# design.net
KiCad netlist of a schematic drawn in EasyEDA Pro
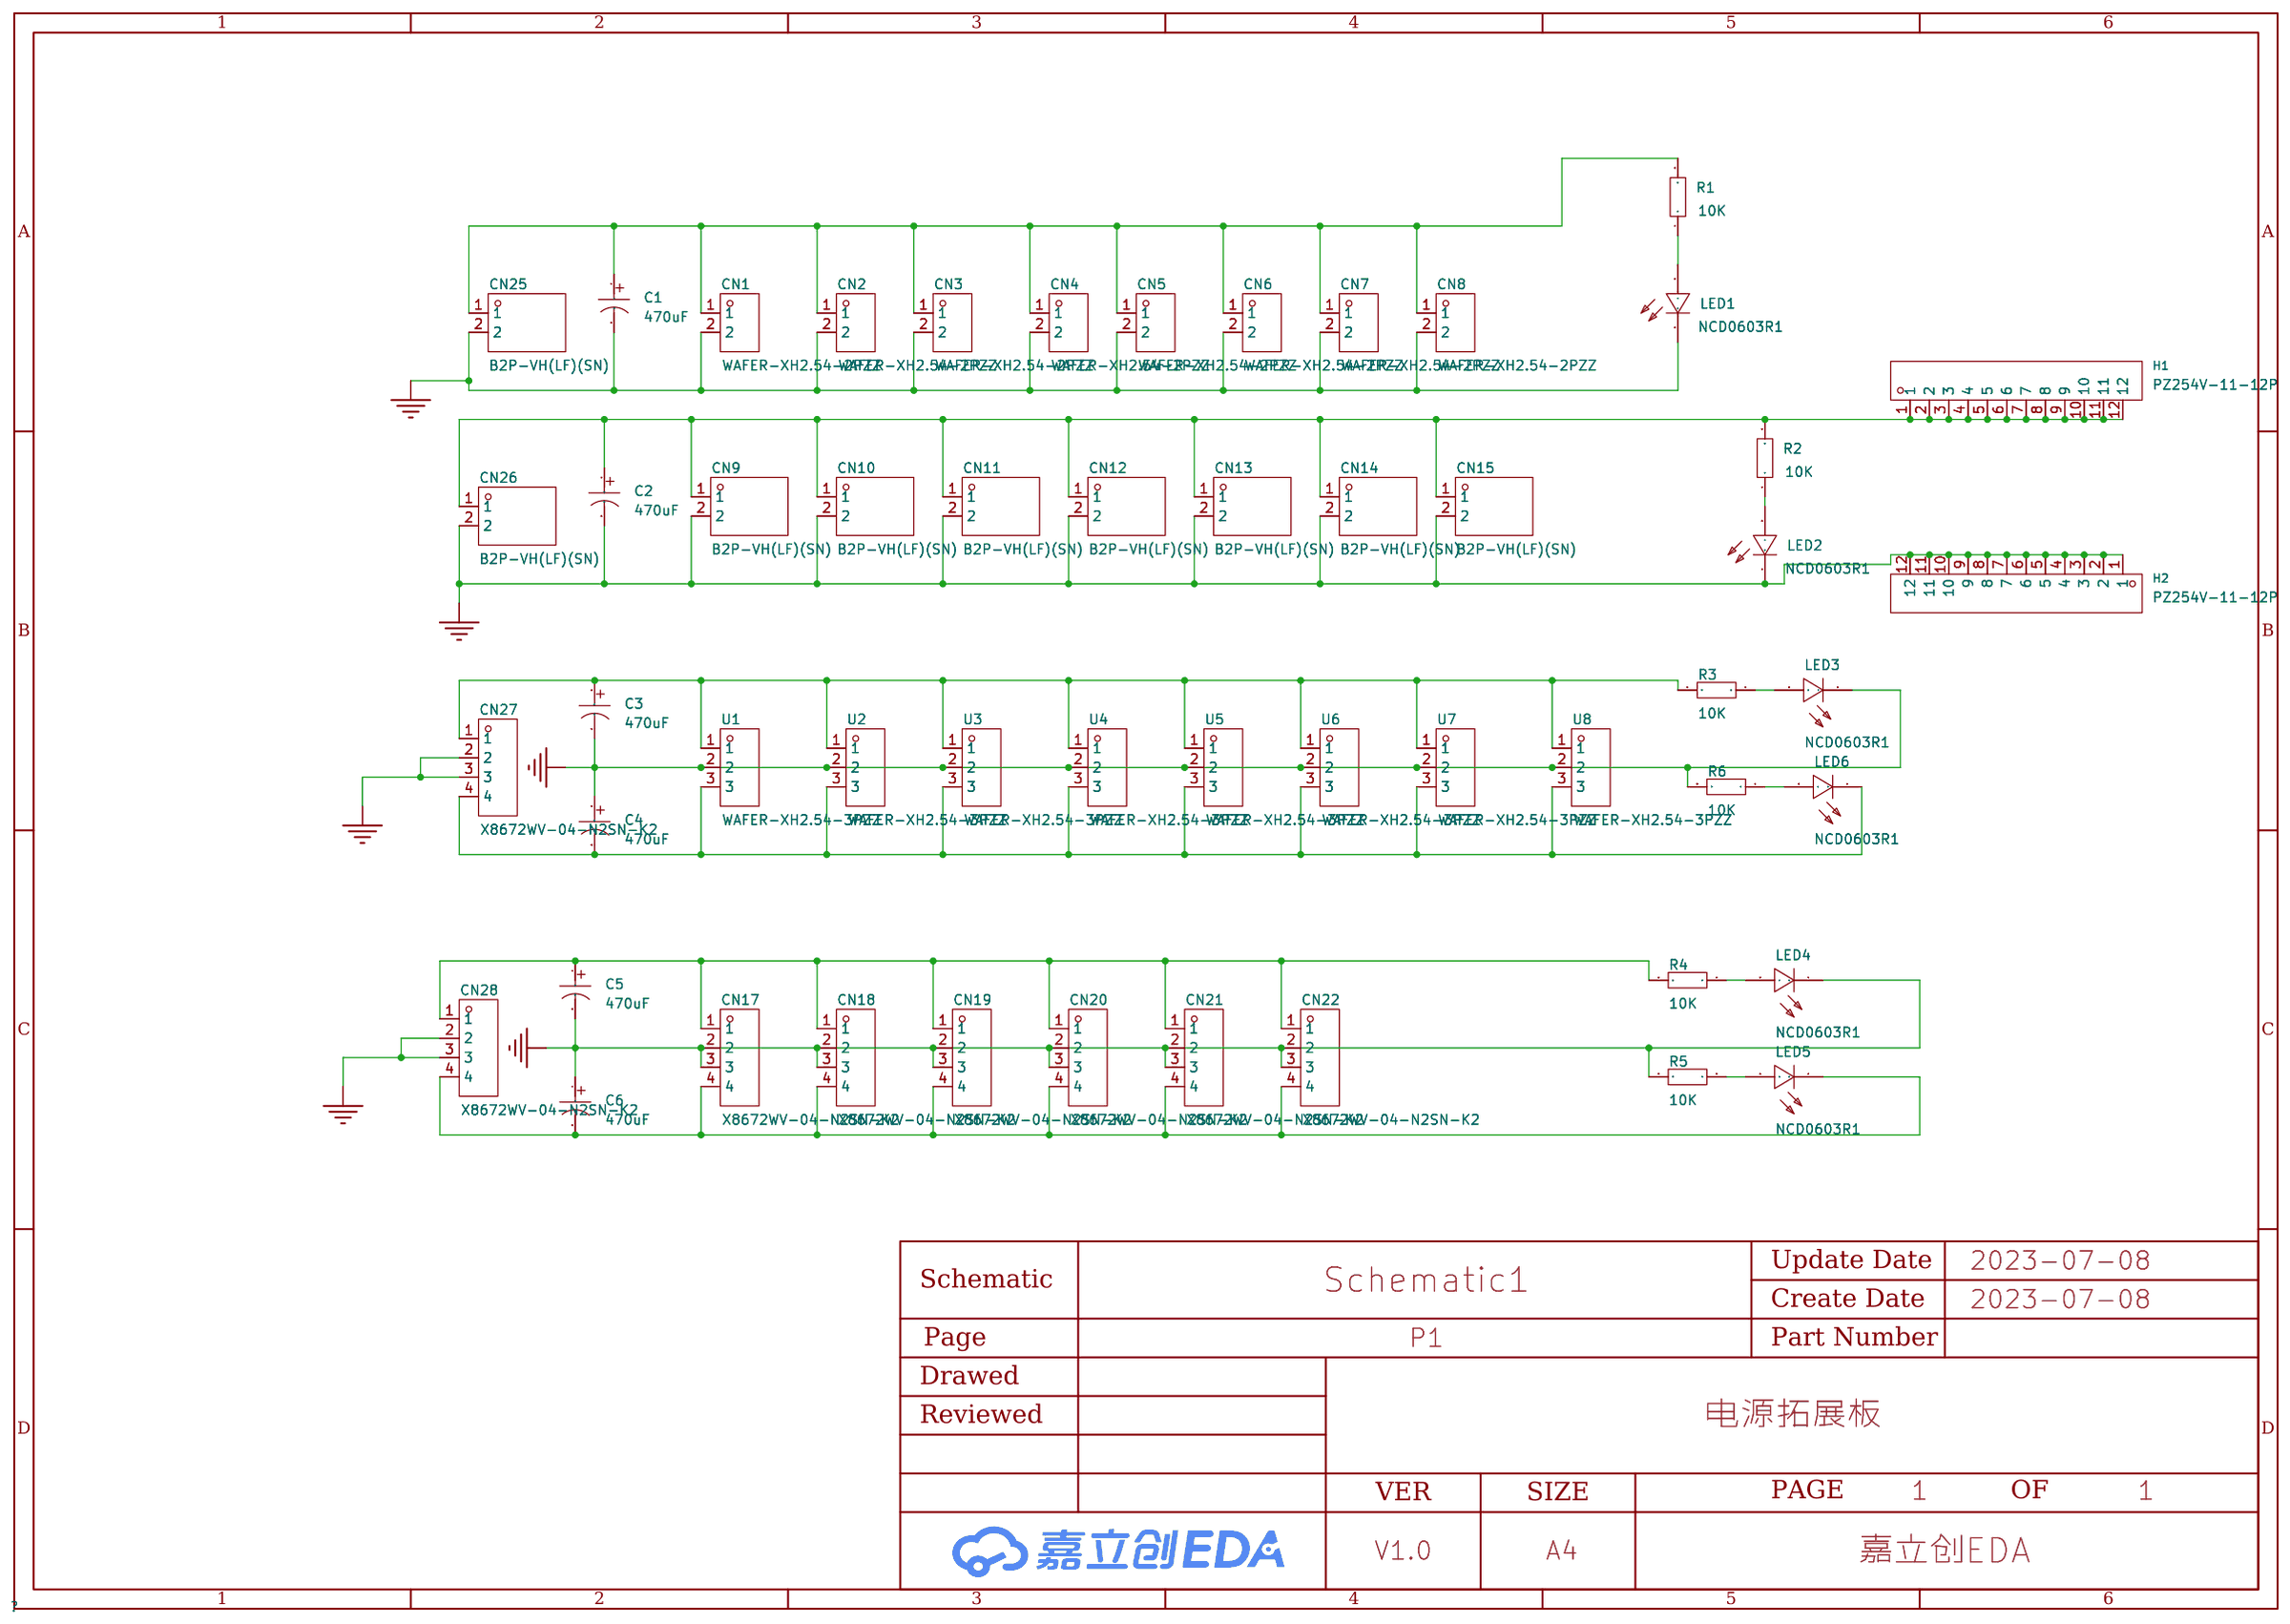
[diagram p0: schematic sheet]

(export (version "E")
  (design (tool "Eeschema 10.0.6"))
  (components
    (comp (ref "C1")
      (value "470uF")
      (footprint "easyedapro:CAP-TH_BD8.0-P3.50-D0.6-FD")
      (description "容值:470uF;精度:±20%;额定电压:25V;")
      (fields
        (field (name "Manufacturer Part") "KM477M025F12RR0VH2FP0")
        (field (name "Manufacturer") "CX(承兴)")
      )
      (libsource (lib "easyedapro") (part "470uF 25V 8*12"))
    )
    (comp (ref "C2")
      (value "470uF")
      (footprint "easyedapro:CAP-TH_BD8.0-P3.50-D0.6-FD")
      (description "容值:470uF;精度:±20%;额定电压:25V;")
      (fields
        (field (name "Manufacturer Part") "KM477M025F12RR0VH2FP0")
        (field (name "Manufacturer") "CX(承兴)")
      )
      (libsource (lib "easyedapro") (part "470uF 25V 8*12"))
    )
    (comp (ref "C3")
      (value "470uF")
      (footprint "easyedapro:CAP-TH_BD8.0-P3.50-D0.6-FD")
      (description "容值:470uF;精度:±20%;额定电压:25V;")
      (fields
        (field (name "Manufacturer Part") "KM477M025F12RR0VH2FP0")
        (field (name "Manufacturer") "CX(承兴)")
      )
      (libsource (lib "easyedapro") (part "470uF 25V 8*12"))
    )
    (comp (ref "C4")
      (value "470uF")
      (footprint "easyedapro:CAP-TH_BD8.0-P3.50-D0.6-FD")
      (description "容值:470uF;精度:±20%;额定电压:25V;")
      (fields
        (field (name "Manufacturer Part") "KM477M025F12RR0VH2FP0")
        (field (name "Manufacturer") "CX(承兴)")
      )
      (libsource (lib "easyedapro") (part "470uF 25V 8*12"))
    )
    (comp (ref "C5")
      (value "470uF")
      (footprint "easyedapro:CAP-TH_BD8.0-P3.50-D0.6-FD")
      (description "容值:470uF;精度:±20%;额定电压:25V;")
      (fields
        (field (name "Manufacturer Part") "KM477M025F12RR0VH2FP0")
        (field (name "Manufacturer") "CX(承兴)")
      )
      (libsource (lib "easyedapro") (part "470uF 25V 8*12"))
    )
    (comp (ref "C6")
      (value "470uF")
      (footprint "easyedapro:CAP-TH_BD8.0-P3.50-D0.6-FD")
      (description "容值:470uF;精度:±20%;额定电压:25V;")
      (fields
        (field (name "Manufacturer Part") "KM477M025F12RR0VH2FP0")
        (field (name "Manufacturer") "CX(承兴)")
      )
      (libsource (lib "easyedapro") (part "470uF 25V 8*12"))
    )
    (comp (ref "CN1")
      (value "WAFER-XH2.54-2PZZ")
      (footprint "easyedapro:CONN-TH_XH2.54-2P")
      (fields (field (name "Manufacturer") "XUNPU(讯普)"))
      (libsource (lib "easyedapro") (part "WAFER-XH2.54-2PZZ"))
    )
    (comp (ref "CN2")
      (value "WAFER-XH2.54-2PZZ")
      (footprint "easyedapro:CONN-TH_XH2.54-2P")
      (fields (field (name "Manufacturer") "XUNPU(讯普)"))
      (libsource (lib "easyedapro") (part "WAFER-XH2.54-2PZZ"))
    )
    (comp (ref "CN3")
      (value "WAFER-XH2.54-2PZZ")
      (footprint "easyedapro:CONN-TH_XH2.54-2P")
      (fields (field (name "Manufacturer") "XUNPU(讯普)"))
      (libsource (lib "easyedapro") (part "WAFER-XH2.54-2PZZ"))
    )
    (comp (ref "CN4")
      (value "WAFER-XH2.54-2PZZ")
      (footprint "easyedapro:CONN-TH_XH2.54-2P")
      (fields (field (name "Manufacturer") "XUNPU(讯普)"))
      (libsource (lib "easyedapro") (part "WAFER-XH2.54-2PZZ"))
    )
    (comp (ref "CN5")
      (value "WAFER-XH2.54-2PZZ")
      (footprint "easyedapro:CONN-TH_XH2.54-2P")
      (fields (field (name "Manufacturer") "XUNPU(讯普)"))
      (libsource (lib "easyedapro") (part "WAFER-XH2.54-2PZZ"))
    )
    (comp (ref "CN6")
      (value "WAFER-XH2.54-2PZZ")
      (footprint "easyedapro:CONN-TH_XH2.54-2P")
      (fields (field (name "Manufacturer") "XUNPU(讯普)"))
      (libsource (lib "easyedapro") (part "WAFER-XH2.54-2PZZ"))
    )
    (comp (ref "CN7")
      (value "WAFER-XH2.54-2PZZ")
      (footprint "easyedapro:CONN-TH_XH2.54-2P")
      (fields (field (name "Manufacturer") "XUNPU(讯普)"))
      (libsource (lib "easyedapro") (part "WAFER-XH2.54-2PZZ"))
    )
    (comp (ref "CN8")
      (value "WAFER-XH2.54-2PZZ")
      (footprint "easyedapro:CONN-TH_XH2.54-2P")
      (fields (field (name "Manufacturer") "XUNPU(讯普)"))
      (libsource (lib "easyedapro") (part "WAFER-XH2.54-2PZZ"))
    )
    (comp (ref "CN9")
      (value "B2P-VH(LF)(SN)")
      (footprint "easyedapro:CONN-TH_B2P-VH-LF-SN")
      (description "参考系列:VH;间距:3.96mm;插针结构:1x2P;排数:1;每排PIN数:2;行距:-;安装方式:-;触头材质:黄铜;")
      (fields (field (name "Manufacturer") "JST"))
      (libsource (lib "easyedapro") (part "B2P-VH (LF)(SN)"))
    )
    (comp (ref "CN10")
      (value "B2P-VH(LF)(SN)")
      (footprint "easyedapro:CONN-TH_B2P-VH-LF-SN")
      (description "参考系列:VH;间距:3.96mm;插针结构:1x2P;排数:1;每排PIN数:2;行距:-;安装方式:-;触头材质:黄铜;")
      (fields (field (name "Manufacturer") "JST"))
      (libsource (lib "easyedapro") (part "B2P-VH (LF)(SN)"))
    )
    (comp (ref "CN11")
      (value "B2P-VH(LF)(SN)")
      (footprint "easyedapro:CONN-TH_B2P-VH-LF-SN")
      (description "参考系列:VH;间距:3.96mm;插针结构:1x2P;排数:1;每排PIN数:2;行距:-;安装方式:-;触头材质:黄铜;")
      (fields (field (name "Manufacturer") "JST"))
      (libsource (lib "easyedapro") (part "B2P-VH (LF)(SN)"))
    )
    (comp (ref "CN12")
      (value "B2P-VH(LF)(SN)")
      (footprint "easyedapro:CONN-TH_B2P-VH-LF-SN")
      (description "参考系列:VH;间距:3.96mm;插针结构:1x2P;排数:1;每排PIN数:2;行距:-;安装方式:-;触头材质:黄铜;")
      (fields (field (name "Manufacturer") "JST"))
      (libsource (lib "easyedapro") (part "B2P-VH (LF)(SN)"))
    )
    (comp (ref "CN13")
      (value "B2P-VH(LF)(SN)")
      (footprint "easyedapro:CONN-TH_B2P-VH-LF-SN")
      (description "参考系列:VH;间距:3.96mm;插针结构:1x2P;排数:1;每排PIN数:2;行距:-;安装方式:-;触头材质:黄铜;")
      (fields (field (name "Manufacturer") "JST"))
      (libsource (lib "easyedapro") (part "B2P-VH (LF)(SN)"))
    )
    (comp (ref "CN14")
      (value "B2P-VH(LF)(SN)")
      (footprint "easyedapro:CONN-TH_B2P-VH-LF-SN")
      (description "参考系列:VH;间距:3.96mm;插针结构:1x2P;排数:1;每排PIN数:2;行距:-;安装方式:-;触头材质:黄铜;")
      (fields (field (name "Manufacturer") "JST"))
      (libsource (lib "easyedapro") (part "B2P-VH (LF)(SN)"))
    )
    (comp (ref "CN15")
      (value "B2P-VH(LF)(SN)")
      (footprint "easyedapro:CONN-TH_B2P-VH-LF-SN")
      (description "参考系列:VH;间距:3.96mm;插针结构:1x2P;排数:1;每排PIN数:2;行距:-;安装方式:-;触头材质:黄铜;")
      (fields (field (name "Manufacturer") "JST"))
      (libsource (lib "easyedapro") (part "B2P-VH (LF)(SN)"))
    )
    (comp (ref "CN17")
      (value "X8672WV-04-N2SN-K2")
      (footprint "easyedapro:CONN-TH_4P-3.96_XKB_X8672WV-04-N2SN-K2")
      (fields (field (name "Manufacturer") "XKB Connectivity(中国星坤)"))
      (libsource (lib "easyedapro") (part "X8672WV-04-N2SN-K2"))
    )
    (comp (ref "CN18")
      (value "X8672WV-04-N2SN-K2")
      (footprint "easyedapro:CONN-TH_4P-3.96_XKB_X8672WV-04-N2SN-K2")
      (fields (field (name "Manufacturer") "XKB Connectivity(中国星坤)"))
      (libsource (lib "easyedapro") (part "X8672WV-04-N2SN-K2"))
    )
    (comp (ref "CN19")
      (value "X8672WV-04-N2SN-K2")
      (footprint "easyedapro:CONN-TH_4P-3.96_XKB_X8672WV-04-N2SN-K2")
      (fields (field (name "Manufacturer") "XKB Connectivity(中国星坤)"))
      (libsource (lib "easyedapro") (part "X8672WV-04-N2SN-K2"))
    )
    (comp (ref "CN20")
      (value "X8672WV-04-N2SN-K2")
      (footprint "easyedapro:CONN-TH_4P-3.96_XKB_X8672WV-04-N2SN-K2")
      (fields (field (name "Manufacturer") "XKB Connectivity(中国星坤)"))
      (libsource (lib "easyedapro") (part "X8672WV-04-N2SN-K2"))
    )
    (comp (ref "CN21")
      (value "X8672WV-04-N2SN-K2")
      (footprint "easyedapro:CONN-TH_4P-3.96_XKB_X8672WV-04-N2SN-K2")
      (fields (field (name "Manufacturer") "XKB Connectivity(中国星坤)"))
      (libsource (lib "easyedapro") (part "X8672WV-04-N2SN-K2"))
    )
    (comp (ref "CN22")
      (value "X8672WV-04-N2SN-K2")
      (footprint "easyedapro:CONN-TH_4P-3.96_XKB_X8672WV-04-N2SN-K2")
      (fields (field (name "Manufacturer") "XKB Connectivity(中国星坤)"))
      (libsource (lib "easyedapro") (part "X8672WV-04-N2SN-K2"))
    )
    (comp (ref "CN25")
      (value "B2P-VH(LF)(SN)")
      (footprint "easyedapro:CONN-TH_B2P-VH-LF-SN")
      (description "参考系列:VH;间距:3.96mm;插针结构:1x2P;排数:1;每排PIN数:2;行距:-;安装方式:-;触头材质:黄铜;")
      (fields (field (name "Manufacturer") "JST"))
      (libsource (lib "easyedapro") (part "B2P-VH (LF)(SN)"))
    )
    (comp (ref "CN26")
      (value "B2P-VH(LF)(SN)")
      (footprint "easyedapro:CONN-TH_B2P-VH-LF-SN")
      (description "参考系列:VH;间距:3.96mm;插针结构:1x2P;排数:1;每排PIN数:2;行距:-;安装方式:-;触头材质:黄铜;")
      (fields (field (name "Manufacturer") "JST"))
      (libsource (lib "easyedapro") (part "B2P-VH (LF)(SN)"))
    )
    (comp (ref "CN27")
      (value "X8672WV-04-N2SN-K2")
      (footprint "easyedapro:CONN-TH_4P-3.96_XKB_X8672WV-04-N2SN-K2")
      (fields (field (name "Manufacturer") "XKB Connectivity(中国星坤)"))
      (libsource (lib "easyedapro") (part "X8672WV-04-N2SN-K2"))
    )
    (comp (ref "CN28")
      (value "X8672WV-04-N2SN-K2")
      (footprint "easyedapro:CONN-TH_4P-3.96_XKB_X8672WV-04-N2SN-K2")
      (fields (field (name "Manufacturer") "XKB Connectivity(中国星坤)"))
      (libsource (lib "easyedapro") (part "X8672WV-04-N2SN-K2"))
    )
    (comp (ref "H1")
      (value "PZ254V-11-12P")
      (footprint "easyedapro:HDR-TH_12P-P2.54-V-M")
      (fields (field (name "Manufacturer") "XFCN(兴飞)"))
      (libsource (lib "easyedapro") (part "PZ254V-11-12P"))
    )
    (comp (ref "H2")
      (value "PZ254V-11-12P")
      (footprint "easyedapro:HDR-TH_12P-P2.54-V-M")
      (fields (field (name "Manufacturer") "XFCN(兴飞)"))
      (libsource (lib "easyedapro") (part "PZ254V-11-12P"))
    )
    (comp (ref "LED1")
      (value "NCD0603R1")
      (footprint "easyedapro:LED0603-RD_RED")
      (description "发光颜色:红灯;")
      (fields (field (name "Manufacturer") "国星光电"))
      (libsource (lib "easyedapro") (part "FC-DA1608HRK-620D"))
    )
    (comp (ref "LED2")
      (value "NCD0603R1")
      (footprint "easyedapro:LED0603-RD_RED")
      (description "发光颜色:红灯;")
      (fields (field (name "Manufacturer") "国星光电"))
      (libsource (lib "easyedapro") (part "FC-DA1608HRK-620D"))
    )
    (comp (ref "LED3")
      (value "NCD0603R1")
      (footprint "easyedapro:LED0603-RD_RED")
      (description "发光颜色:红灯;")
      (fields (field (name "Manufacturer") "国星光电"))
      (libsource (lib "easyedapro") (part "FC-DA1608HRK-620D"))
    )
    (comp (ref "LED4")
      (value "NCD0603R1")
      (footprint "easyedapro:LED0603-RD_RED")
      (description "发光颜色:红灯;")
      (fields (field (name "Manufacturer") "国星光电"))
      (libsource (lib "easyedapro") (part "FC-DA1608HRK-620D"))
    )
    (comp (ref "LED5")
      (value "NCD0603R1")
      (footprint "easyedapro:LED0603-RD_RED")
      (description "发光颜色:红灯;")
      (fields (field (name "Manufacturer") "国星光电"))
      (libsource (lib "easyedapro") (part "FC-DA1608HRK-620D"))
    )
    (comp (ref "LED6")
      (value "NCD0603R1")
      (footprint "easyedapro:LED0603-RD_RED")
      (description "发光颜色:红灯;")
      (fields (field (name "Manufacturer") "国星光电"))
      (libsource (lib "easyedapro") (part "FC-DA1608HRK-620D"))
    )
    (comp (ref "R1") (value "10K") (footprint "easyedapro:R0603") (libsource (lib "easyedapro") (part "电阻")))
    (comp (ref "R2") (value "10K") (footprint "easyedapro:R0603") (libsource (lib "easyedapro") (part "电阻")))
    (comp (ref "R3") (value "10K") (footprint "easyedapro:R0603") (libsource (lib "easyedapro") (part "电阻")))
    (comp (ref "R4") (value "10K") (footprint "easyedapro:R0603") (libsource (lib "easyedapro") (part "电阻")))
    (comp (ref "R5") (value "10K") (footprint "easyedapro:R0603") (libsource (lib "easyedapro") (part "电阻")))
    (comp (ref "R6") (value "10K") (footprint "easyedapro:R0603") (libsource (lib "easyedapro") (part "电阻")))
    (comp (ref "U1")
      (value "WAFER-XH2.54-3PZZ")
      (footprint "easyedapro:CONN-TH_3P-P2.50_WAFER-XH2.54-3PZZ")
      (fields (field (name "Manufacturer") "XUNPU(讯普)"))
      (libsource (lib "easyedapro") (part "WAFER-XH2.54-3PZZ"))
    )
    (comp (ref "U2")
      (value "WAFER-XH2.54-3PZZ")
      (footprint "easyedapro:CONN-TH_3P-P2.50_WAFER-XH2.54-3PZZ")
      (fields (field (name "Manufacturer") "XUNPU(讯普)"))
      (libsource (lib "easyedapro") (part "WAFER-XH2.54-3PZZ"))
    )
    (comp (ref "U3")
      (value "WAFER-XH2.54-3PZZ")
      (footprint "easyedapro:CONN-TH_3P-P2.50_WAFER-XH2.54-3PZZ")
      (fields (field (name "Manufacturer") "XUNPU(讯普)"))
      (libsource (lib "easyedapro") (part "WAFER-XH2.54-3PZZ"))
    )
    (comp (ref "U4")
      (value "WAFER-XH2.54-3PZZ")
      (footprint "easyedapro:CONN-TH_3P-P2.50_WAFER-XH2.54-3PZZ")
      (fields (field (name "Manufacturer") "XUNPU(讯普)"))
      (libsource (lib "easyedapro") (part "WAFER-XH2.54-3PZZ"))
    )
    (comp (ref "U5")
      (value "WAFER-XH2.54-3PZZ")
      (footprint "easyedapro:CONN-TH_3P-P2.50_WAFER-XH2.54-3PZZ")
      (fields (field (name "Manufacturer") "XUNPU(讯普)"))
      (libsource (lib "easyedapro") (part "WAFER-XH2.54-3PZZ"))
    )
    (comp (ref "U6")
      (value "WAFER-XH2.54-3PZZ")
      (footprint "easyedapro:CONN-TH_3P-P2.50_WAFER-XH2.54-3PZZ")
      (fields (field (name "Manufacturer") "XUNPU(讯普)"))
      (libsource (lib "easyedapro") (part "WAFER-XH2.54-3PZZ"))
    )
    (comp (ref "U7")
      (value "WAFER-XH2.54-3PZZ")
      (footprint "easyedapro:CONN-TH_3P-P2.50_WAFER-XH2.54-3PZZ")
      (fields (field (name "Manufacturer") "XUNPU(讯普)"))
      (libsource (lib "easyedapro") (part "WAFER-XH2.54-3PZZ"))
    )
    (comp (ref "U8")
      (value "WAFER-XH2.54-3PZZ")
      (footprint "easyedapro:CONN-TH_3P-P2.50_WAFER-XH2.54-3PZZ")
      (fields (field (name "Manufacturer") "XUNPU(讯普)"))
      (libsource (lib "easyedapro") (part "WAFER-XH2.54-3PZZ"))
    )
  )
  (nets
    (net (code "1") (name "GND") (class "Default")
      (node (ref "C1") (pin "2") (pinfunction "2_2") (pintype "input"))
      (node (ref "C2") (pin "2") (pinfunction "2_2") (pintype "input"))
      (node (ref "C3") (pin "2") (pinfunction "2_2") (pintype "input"))
      (node (ref "C4") (pin "1") (pinfunction "1_1") (pintype "input"))
      (node (ref "C5") (pin "2") (pinfunction "2_2") (pintype "input"))
      (node (ref "C6") (pin "1") (pinfunction "1_1") (pintype "input"))
      (node (ref "CN1") (pin "2") (pinfunction "2_2") (pintype "input"))
      (node (ref "CN10") (pin "2") (pinfunction "2_2") (pintype "input"))
      (node (ref "CN11") (pin "2") (pinfunction "2_2") (pintype "input"))
      (node (ref "CN12") (pin "2") (pinfunction "2_2") (pintype "input"))
      (node (ref "CN13") (pin "2") (pinfunction "2_2") (pintype "input"))
      (node (ref "CN14") (pin "2") (pinfunction "2_2") (pintype "input"))
      (node (ref "CN15") (pin "2") (pinfunction "2_2") (pintype "input"))
      (node (ref "CN17") (pin "2") (pinfunction "2_2") (pintype "input"))
      (node (ref "CN17") (pin "3") (pinfunction "3_3") (pintype "input"))
      (node (ref "CN18") (pin "2") (pinfunction "2_2") (pintype "input"))
      (node (ref "CN18") (pin "3") (pinfunction "3_3") (pintype "input"))
      (node (ref "CN19") (pin "2") (pinfunction "2_2") (pintype "input"))
      (node (ref "CN19") (pin "3") (pinfunction "3_3") (pintype "input"))
      (node (ref "CN2") (pin "2") (pinfunction "2_2") (pintype "input"))
      (node (ref "CN20") (pin "2") (pinfunction "2_2") (pintype "input"))
      (node (ref "CN20") (pin "3") (pinfunction "3_3") (pintype "input"))
      (node (ref "CN21") (pin "2") (pinfunction "2_2") (pintype "input"))
      (node (ref "CN21") (pin "3") (pinfunction "3_3") (pintype "input"))
      (node (ref "CN22") (pin "2") (pinfunction "2_2") (pintype "input"))
      (node (ref "CN22") (pin "3") (pinfunction "3_3") (pintype "input"))
      (node (ref "CN25") (pin "2") (pinfunction "2_2") (pintype "input"))
      (node (ref "CN26") (pin "2") (pinfunction "2_2") (pintype "input"))
      (node (ref "CN27") (pin "2") (pinfunction "2_2") (pintype "input"))
      (node (ref "CN27") (pin "3") (pinfunction "3_3") (pintype "input"))
      (node (ref "CN28") (pin "2") (pinfunction "2_2") (pintype "input"))
      (node (ref "CN28") (pin "3") (pinfunction "3_3") (pintype "input"))
      (node (ref "CN3") (pin "2") (pinfunction "2_2") (pintype "input"))
      (node (ref "CN4") (pin "2") (pinfunction "2_2") (pintype "input"))
      (node (ref "CN5") (pin "2") (pinfunction "2_2") (pintype "input"))
      (node (ref "CN6") (pin "2") (pinfunction "2_2") (pintype "input"))
      (node (ref "CN7") (pin "2") (pinfunction "2_2") (pintype "input"))
      (node (ref "CN8") (pin "2") (pinfunction "2_2") (pintype "input"))
      (node (ref "CN9") (pin "2") (pinfunction "2_2") (pintype "input"))
      (node (ref "H2") (pin "1") (pinfunction "1_1") (pintype "input"))
      (node (ref "H2") (pin "10") (pinfunction "10_10") (pintype "input"))
      (node (ref "H2") (pin "11") (pinfunction "11_11") (pintype "input"))
      (node (ref "H2") (pin "12") (pinfunction "12_12") (pintype "input"))
      (node (ref "H2") (pin "2") (pinfunction "2_2") (pintype "input"))
      (node (ref "H2") (pin "3") (pinfunction "3_3") (pintype "input"))
      (node (ref "H2") (pin "4") (pinfunction "4_4") (pintype "input"))
      (node (ref "H2") (pin "5") (pinfunction "5_5") (pintype "input"))
      (node (ref "H2") (pin "6") (pinfunction "6_6") (pintype "input"))
      (node (ref "H2") (pin "7") (pinfunction "7_7") (pintype "input"))
      (node (ref "H2") (pin "8") (pinfunction "8_8") (pintype "input"))
      (node (ref "H2") (pin "9") (pinfunction "9_9") (pintype "input"))
      (node (ref "LED1") (pin "1") (pinfunction "K_1") (pintype "input"))
      (node (ref "LED2") (pin "1") (pinfunction "K_1") (pintype "input"))
      (node (ref "LED3") (pin "1") (pinfunction "K_1") (pintype "input"))
      (node (ref "LED4") (pin "1") (pinfunction "K_1") (pintype "input"))
      (node (ref "R5") (pin "2") (pinfunction "2_2") (pintype "input"))
      (node (ref "R6") (pin "2") (pinfunction "2_2") (pintype "input"))
      (node (ref "U1") (pin "2") (pinfunction "2_2") (pintype "input"))
      (node (ref "U2") (pin "2") (pinfunction "2_2") (pintype "input"))
      (node (ref "U3") (pin "2") (pinfunction "2_2") (pintype "input"))
      (node (ref "U4") (pin "2") (pinfunction "2_2") (pintype "input"))
      (node (ref "U5") (pin "2") (pinfunction "2_2") (pintype "input"))
      (node (ref "U6") (pin "2") (pinfunction "2_2") (pintype "input"))
      (node (ref "U7") (pin "2") (pinfunction "2_2") (pintype "input"))
      (node (ref "U8") (pin "2") (pinfunction "2_2") (pintype "input"))
    )
    (net (code "2") (name "Net-(C1-Pad1)") (class "Default")
      (node (ref "C1") (pin "1") (pinfunction "1_1") (pintype "input"))
      (node (ref "CN1") (pin "1") (pinfunction "1_1") (pintype "input"))
      (node (ref "CN2") (pin "1") (pinfunction "1_1") (pintype "input"))
      (node (ref "CN25") (pin "1") (pinfunction "1_1") (pintype "input"))
      (node (ref "CN3") (pin "1") (pinfunction "1_1") (pintype "input"))
      (node (ref "CN4") (pin "1") (pinfunction "1_1") (pintype "input"))
      (node (ref "CN5") (pin "1") (pinfunction "1_1") (pintype "input"))
      (node (ref "CN6") (pin "1") (pinfunction "1_1") (pintype "input"))
      (node (ref "CN7") (pin "1") (pinfunction "1_1") (pintype "input"))
      (node (ref "CN8") (pin "1") (pinfunction "1_1") (pintype "input"))
      (node (ref "R1") (pin "2") (pinfunction "2_2") (pintype "input"))
    )
    (net (code "3") (name "Net-(C2-Pad1)") (class "Default")
      (node (ref "C2") (pin "1") (pinfunction "1_1") (pintype "input"))
      (node (ref "CN10") (pin "1") (pinfunction "1_1") (pintype "input"))
      (node (ref "CN11") (pin "1") (pinfunction "1_1") (pintype "input"))
      (node (ref "CN12") (pin "1") (pinfunction "1_1") (pintype "input"))
      (node (ref "CN13") (pin "1") (pinfunction "1_1") (pintype "input"))
      (node (ref "CN14") (pin "1") (pinfunction "1_1") (pintype "input"))
      (node (ref "CN15") (pin "1") (pinfunction "1_1") (pintype "input"))
      (node (ref "CN26") (pin "1") (pinfunction "1_1") (pintype "input"))
      (node (ref "CN9") (pin "1") (pinfunction "1_1") (pintype "input"))
      (node (ref "H1") (pin "1") (pinfunction "1_1") (pintype "input"))
      (node (ref "H1") (pin "10") (pinfunction "10_10") (pintype "input"))
      (node (ref "H1") (pin "11") (pinfunction "11_11") (pintype "input"))
      (node (ref "H1") (pin "12") (pinfunction "12_12") (pintype "input"))
      (node (ref "H1") (pin "2") (pinfunction "2_2") (pintype "input"))
      (node (ref "H1") (pin "3") (pinfunction "3_3") (pintype "input"))
      (node (ref "H1") (pin "4") (pinfunction "4_4") (pintype "input"))
      (node (ref "H1") (pin "5") (pinfunction "5_5") (pintype "input"))
      (node (ref "H1") (pin "6") (pinfunction "6_6") (pintype "input"))
      (node (ref "H1") (pin "7") (pinfunction "7_7") (pintype "input"))
      (node (ref "H1") (pin "8") (pinfunction "8_8") (pintype "input"))
      (node (ref "H1") (pin "9") (pinfunction "9_9") (pintype "input"))
      (node (ref "R2") (pin "2") (pinfunction "2_2") (pintype "input"))
    )
    (net (code "4") (name "Net-(C3-Pad1)") (class "Default")
      (node (ref "C3") (pin "1") (pinfunction "1_1") (pintype "input"))
      (node (ref "CN27") (pin "1") (pinfunction "1_1") (pintype "input"))
      (node (ref "R3") (pin "2") (pinfunction "2_2") (pintype "input"))
      (node (ref "U1") (pin "1") (pinfunction "1_1") (pintype "input"))
      (node (ref "U2") (pin "1") (pinfunction "1_1") (pintype "input"))
      (node (ref "U3") (pin "1") (pinfunction "1_1") (pintype "input"))
      (node (ref "U4") (pin "1") (pinfunction "1_1") (pintype "input"))
      (node (ref "U5") (pin "1") (pinfunction "1_1") (pintype "input"))
      (node (ref "U6") (pin "1") (pinfunction "1_1") (pintype "input"))
      (node (ref "U7") (pin "1") (pinfunction "1_1") (pintype "input"))
      (node (ref "U8") (pin "1") (pinfunction "1_1") (pintype "input"))
    )
    (net (code "5") (name "Net-(C5-Pad1)") (class "Default")
      (node (ref "C5") (pin "1") (pinfunction "1_1") (pintype "input"))
      (node (ref "CN17") (pin "1") (pinfunction "1_1") (pintype "input"))
      (node (ref "CN18") (pin "1") (pinfunction "1_1") (pintype "input"))
      (node (ref "CN19") (pin "1") (pinfunction "1_1") (pintype "input"))
      (node (ref "CN20") (pin "1") (pinfunction "1_1") (pintype "input"))
      (node (ref "CN21") (pin "1") (pinfunction "1_1") (pintype "input"))
      (node (ref "CN22") (pin "1") (pinfunction "1_1") (pintype "input"))
      (node (ref "CN28") (pin "1") (pinfunction "1_1") (pintype "input"))
      (node (ref "R4") (pin "2") (pinfunction "2_2") (pintype "input"))
    )
    (net (code "6") (name "Net-(LED1-A)") (class "Default")
      (node (ref "LED1") (pin "2") (pinfunction "A_2") (pintype "input"))
      (node (ref "R1") (pin "1") (pinfunction "1_1") (pintype "input"))
    )
    (net (code "7") (name "Net-(LED2-A)") (class "Default")
      (node (ref "LED2") (pin "2") (pinfunction "A_2") (pintype "input"))
      (node (ref "R2") (pin "1") (pinfunction "1_1") (pintype "input"))
    )
    (net (code "8") (name "Net-(LED3-A)") (class "Default")
      (node (ref "LED3") (pin "2") (pinfunction "A_2") (pintype "input"))
      (node (ref "R3") (pin "1") (pinfunction "1_1") (pintype "input"))
    )
    (net (code "9") (name "Net-(LED4-A)") (class "Default")
      (node (ref "LED4") (pin "2") (pinfunction "A_2") (pintype "input"))
      (node (ref "R4") (pin "1") (pinfunction "1_1") (pintype "input"))
    )
    (net (code "10") (name "Net-(LED5-A)") (class "Default")
      (node (ref "LED5") (pin "2") (pinfunction "A_2") (pintype "input"))
      (node (ref "R5") (pin "1") (pinfunction "1_1") (pintype "input"))
    )
    (net (code "11") (name "Net-(LED5-K)") (class "Default")
      (node (ref "C6") (pin "2") (pinfunction "2_2") (pintype "input"))
      (node (ref "CN17") (pin "4") (pinfunction "4_4") (pintype "input"))
      (node (ref "CN18") (pin "4") (pinfunction "4_4") (pintype "input"))
      (node (ref "CN19") (pin "4") (pinfunction "4_4") (pintype "input"))
      (node (ref "CN20") (pin "4") (pinfunction "4_4") (pintype "input"))
      (node (ref "CN21") (pin "4") (pinfunction "4_4") (pintype "input"))
      (node (ref "CN22") (pin "4") (pinfunction "4_4") (pintype "input"))
      (node (ref "CN28") (pin "4") (pinfunction "4_4") (pintype "input"))
      (node (ref "LED5") (pin "1") (pinfunction "K_1") (pintype "input"))
    )
    (net (code "12") (name "Net-(LED6-A)") (class "Default")
      (node (ref "LED6") (pin "2") (pinfunction "A_2") (pintype "input"))
      (node (ref "R6") (pin "1") (pinfunction "1_1") (pintype "input"))
    )
    (net (code "13") (name "Net-(LED6-K)") (class "Default")
      (node (ref "C4") (pin "2") (pinfunction "2_2") (pintype "input"))
      (node (ref "CN27") (pin "4") (pinfunction "4_4") (pintype "input"))
      (node (ref "LED6") (pin "1") (pinfunction "K_1") (pintype "input"))
      (node (ref "U1") (pin "3") (pinfunction "3_3") (pintype "input"))
      (node (ref "U2") (pin "3") (pinfunction "3_3") (pintype "input"))
      (node (ref "U3") (pin "3") (pinfunction "3_3") (pintype "input"))
      (node (ref "U4") (pin "3") (pinfunction "3_3") (pintype "input"))
      (node (ref "U5") (pin "3") (pinfunction "3_3") (pintype "input"))
      (node (ref "U6") (pin "3") (pinfunction "3_3") (pintype "input"))
      (node (ref "U7") (pin "3") (pinfunction "3_3") (pintype "input"))
      (node (ref "U8") (pin "3") (pinfunction "3_3") (pintype "input"))
    )
  )
)
